# Sheet4.net
KiCad netlist of a schematic drawn in Altium Designer
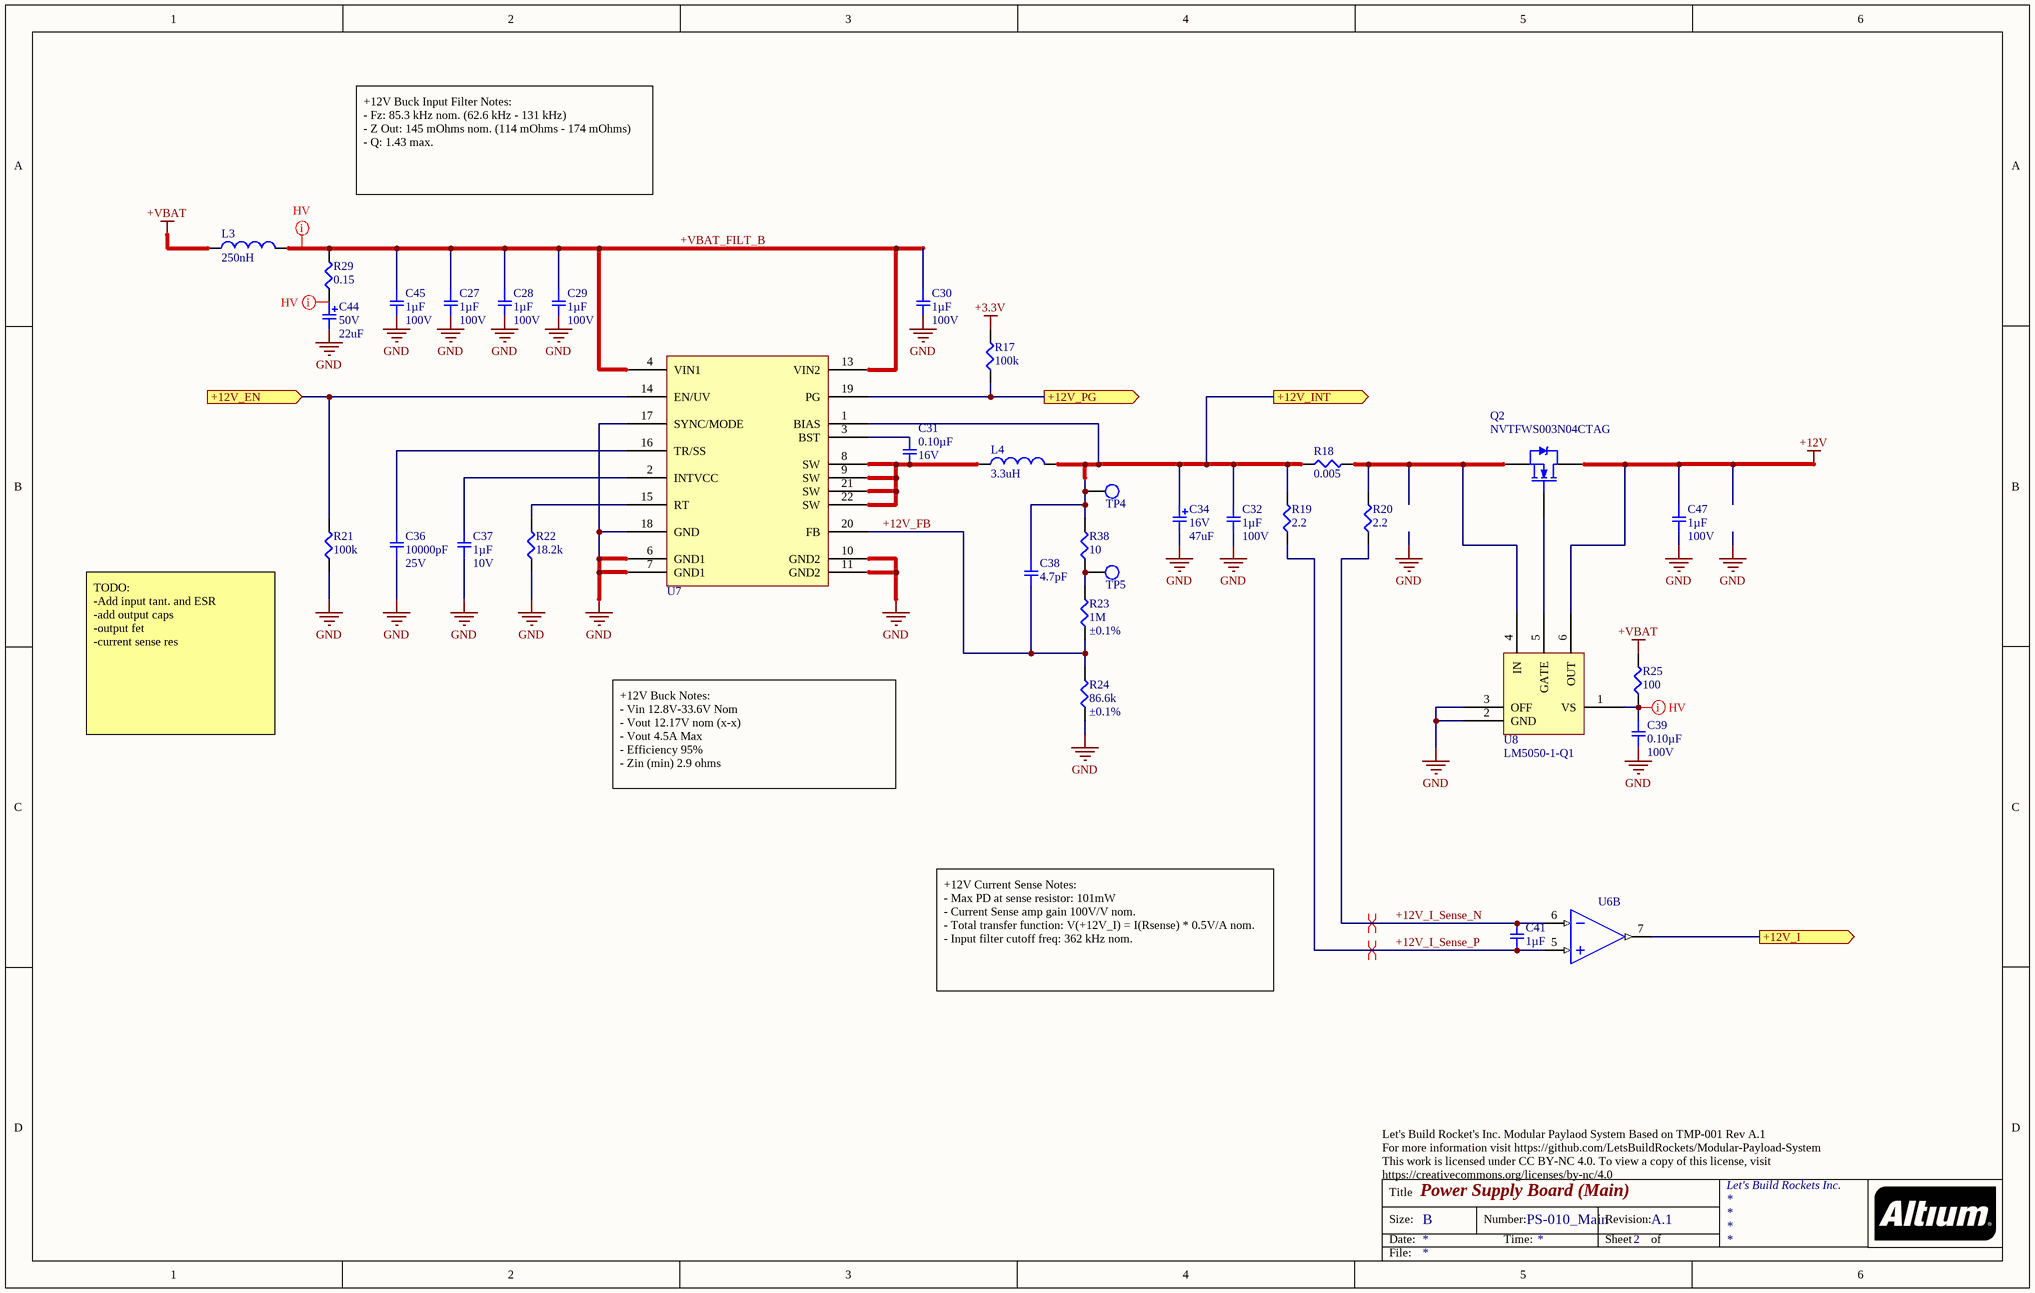
[diagram p0: Sheet4.SchDoc]

(export (version "E")
  (design (tool "Eeschema 10.0.6"))
  (components
    (comp (ref "C27")
      (value "1µF")
      (footprint "SMD-0805C")
      (description "CAP CER 1UF 100V X7S 0805")
      (fields
        (field (name "DIGI-KEY PART NUMBER") "490-10918-1-ND")
        (field (name "PART NUMBER") "GRJ21BC72A105KE11L")
        (field (name "VOLTAGE") "100V")
      )
      (libsource (lib "capacitor_murata_0805") (part "GRJ21BC72A105KE11L"))
    )
    (comp (ref "C28")
      (value "1µF")
      (footprint "SMD-0805C")
      (description "CAP CER 1UF 100V X7S 0805")
      (fields
        (field (name "DIGI-KEY PART NUMBER") "490-10918-1-ND")
        (field (name "PART NUMBER") "GRJ21BC72A105KE11L")
        (field (name "VOLTAGE") "100V")
      )
      (libsource (lib "capacitor_murata_0805") (part "GRJ21BC72A105KE11L"))
    )
    (comp (ref "C29")
      (value "1µF")
      (footprint "SMD-0805C")
      (description "CAP CER 1UF 100V X7S 0805")
      (fields
        (field (name "DIGI-KEY PART NUMBER") "490-10918-1-ND")
        (field (name "PART NUMBER") "GRJ21BC72A105KE11L")
        (field (name "VOLTAGE") "100V")
      )
      (libsource (lib "capacitor_murata_0805") (part "GRJ21BC72A105KE11L"))
    )
    (comp (ref "C30")
      (value "1µF")
      (footprint "SMD-0805C")
      (description "CAP CER 1UF 100V X7S 0805")
      (fields
        (field (name "DIGI-KEY PART NUMBER") "490-10918-1-ND")
        (field (name "PART NUMBER") "GRJ21BC72A105KE11L")
        (field (name "VOLTAGE") "100V")
      )
      (libsource (lib "capacitor_murata_0805") (part "GRJ21BC72A105KE11L"))
    )
    (comp (ref "C31")
      (value "0.10µF")
      (footprint "SMD-0402C")
      (description "CAP CER 0.1UF 16V X7R 0402")
      (fields
        (field (name "DIGI-KEY PART NUMBER") "490-4759-1-ND")
        (field (name "PART NUMBER") "GCM155R71C104KA55D")
        (field (name "VOLTAGE") "16V")
      )
      (libsource (lib "capacitor_murata_0402") (part "GCM155R71C104KA55D"))
    )
    (comp (ref "C32")
      (value "1µF")
      (footprint "SMD-0805C")
      (description "CAP CER 1UF 100V X7S 0805")
      (fields
        (field (name "DIGI-KEY PART NUMBER") "490-10918-1-ND")
        (field (name "PART NUMBER") "GRJ21BC72A105KE11L")
        (field (name "VOLTAGE") "100V")
      )
      (libsource (lib "capacitor_murata_0805") (part "GRJ21BC72A105KE11L"))
    )
    (comp (ref "C34")
      (value "47uF")
      (footprint "KEMET W - CAPMP7343X15N")
      (fields (field (name "VOLTAGE") "16V") (field (name "Comment") "T521W476M016ATE045"))
      (libsource (lib "KEMET") (part "T521W476M016ATE045"))
    )
    (comp (ref "C36")
      (value "10000pF")
      (footprint "SMD-0402C")
      (description "CAP CER 10000PF 25V X7R 0402")
      (fields
        (field (name "DIGI-KEY PART NUMBER") "490-6043-1-ND")
        (field (name "PART NUMBER") "GCM155R71E103KA37D")
        (field (name "VOLTAGE") "25V")
      )
      (libsource (lib "capacitor_murata_0402") (part "GCM155R71E103KA37D"))
    )
    (comp (ref "C37")
      (value "1µF")
      (footprint "SMD-0402C")
      (description "CAP CER 1UF 10V X7S 0402")
      (fields
        (field (name "DIGI-KEY PART NUMBER") "490-13409-1-ND")
        (field (name "PART NUMBER") "GCM155C71A105KE38D")
        (field (name "VOLTAGE") "10V")
      )
      (libsource (lib "capacitor_murata_0402") (part "GCM155C71A105KE38D"))
    )
    (comp (ref "C38")
      (value "4.7pF")
      (footprint "SMD-0402C")
      (description "CAP CER 4.7PF 50V NP0 0402")
      (fields
        (field (name "DIGI-KEY PART NUMBER") "490-12652-1-ND")
        (field (name "PART NUMBER") "GCM1555C1H4R7CA16D")
      )
      (libsource (lib "capacitor_murata_0402") (part "GCM1555C1H4R7CA16D"))
    )
    (comp (ref "C39")
      (value "0.10µF")
      (footprint "SMD-0603C")
      (description "CAP CER 0.1UF 100V X7R 0603")
      (fields
        (field (name "DIGI-KEY PART NUMBER") "490-3285-1-ND")
        (field (name "PART NUMBER") "GRM188R72A104KA35D")
        (field (name "VOLTAGE") "100V")
      )
      (libsource (lib "capacitor_murata_0603") (part "GRM188R72A104KA35D"))
    )
    (comp (ref "C41")
      (value "1µF")
      (footprint "SMD-0402C")
      (description "CAP CER 1UF 10V X7S 0402")
      (fields
        (field (name "DIGI-KEY PART NUMBER") "490-13409-1-ND")
        (field (name "PART NUMBER") "GCM155C71A105KE38D")
      )
      (libsource (lib "capacitor_murata_0402") (part "GCM155C71A105KE38D"))
    )
    (comp (ref "C44")
      (value "22uF")
      (footprint "KEMET D - CAPMP7343X31N")
      (fields (field (name "VOLTAGE") "50V") (field (name "Comment") "T521D226M050ATE090"))
      (libsource (lib "KEMET") (part "T521D226M050ATE090"))
    )
    (comp (ref "C45")
      (value "1µF")
      (footprint "SMD-0805C")
      (description "CAP CER 1UF 100V X7S 0805")
      (fields
        (field (name "DIGI-KEY PART NUMBER") "490-10918-1-ND")
        (field (name "PART NUMBER") "GRJ21BC72A105KE11L")
        (field (name "VOLTAGE") "100V")
      )
      (libsource (lib "capacitor_murata_0805") (part "GRJ21BC72A105KE11L"))
    )
    (comp (ref "C47")
      (value "1µF")
      (footprint "SMD-0805C")
      (description "CAP CER 1UF 100V X7S 0805")
      (fields
        (field (name "DIGI-KEY PART NUMBER") "490-10918-1-ND")
        (field (name "PART NUMBER") "GRJ21BC72A105KE11L")
        (field (name "VOLTAGE") "100V")
      )
      (libsource (lib "capacitor_murata_0805") (part "GRJ21BC72A105KE11L"))
    )
    (comp (ref "L3")
      (value "250nH")
      (footprint "INDM4040X21N (XGL4020)")
      (fields (field (name "Comment") "XGL4020-251ME"))
      (libsource (lib "ModularPayload") (part "XGL4020-251ME"))
    )
    (comp (ref "L4")
      (value "3.3uH")
      (footprint "INDM7050X50N (Wurth)")
      (fields (field (name "TOLERANCE") "20%") (field (name "Comment") "744314330"))
      (libsource (lib "ModularPayload") (part "744314330"))
    )
    (comp (ref "Q2")
      (value "NVTFWS003N04CTAG")
      (footprint "DFN065P305X80-8N")
      (libsource (lib "ModularPayload") (part "NVTFWS003N04CTAG"))
    )
    (comp (ref "R17")
      (value "100k")
      (footprint "SMD-0402-RES")
      (description "RES SMD 100K OHM 5% 1/10W 0402")
      (fields (field (name "PART NUMBER") "ERJ-2GEJ104X") (field (name "DIGI-KEY PART NUMBER") "P100KJCT-ND"))
      (libsource (lib "Panasonic_ERJ_0402") (part "ERJ-2GEJ104X"))
    )
    (comp (ref "R18")
      (value "0.005")
      (footprint "SMD-0603-RES")
      (description "RES SMD 0.005 OHM 1% 1/4W 0603")
      (fields
        (field (name "PART NUMBER") "ERJ-3LWFR005V")
        (field (name "DIGI-KEY PART NUMBER") "P19182CT-ND")
      )
      (libsource (lib "Panasonic_ERJ_0603") (part "ERJ-3LWFR005V"))
    )
    (comp (ref "R19")
      (value "2.2")
      (footprint "SMD-0603-RES")
      (description "RES SMD 2.2 OHM 1% 1/10W 0603")
      (fields (field (name "PART NUMBER") "ERJ-3RQF2R2V") (field (name "DIGI-KEY PART NUMBER") "P2.2AJCT-ND"))
      (libsource (lib "Panasonic_ERJ_0603") (part "ERJ-3RQF2R2V"))
    )
    (comp (ref "R20")
      (value "2.2")
      (footprint "SMD-0603-RES")
      (description "RES SMD 2.2 OHM 1% 1/10W 0603")
      (fields (field (name "PART NUMBER") "ERJ-3RQF2R2V") (field (name "DIGI-KEY PART NUMBER") "P2.2AJCT-ND"))
      (libsource (lib "Panasonic_ERJ_0603") (part "ERJ-3RQF2R2V"))
    )
    (comp (ref "R21")
      (value "100k")
      (footprint "SMD-0402-RES")
      (description "RES SMD 100K OHM 5% 1/10W 0402")
      (fields (field (name "PART NUMBER") "ERJ-2GEJ104X") (field (name "DIGI-KEY PART NUMBER") "P100KJCT-ND"))
      (libsource (lib "Panasonic_ERJ_0402") (part "ERJ-2GEJ104X"))
    )
    (comp (ref "R22")
      (value "18.2k")
      (footprint "SMD-0402-RES")
      (description "RES SMD 18.2K OHM 1% 1/10W 0402")
      (fields
        (field (name "PART NUMBER") "ERJ-2RKF1822X")
        (field (name "DIGI-KEY PART NUMBER") "P18.2KLCT-ND")
      )
      (libsource (lib "Panasonic_ERJ_0402") (part "ERJ-2RKF1822X"))
    )
    (comp (ref "R23")
      (value "1M")
      (footprint "SMD-0805-RES")
      (description "RES SMD 1M OHM 0.1% 1/4W 0805")
      (fields
        (field (name "PART NUMBER") "ERJ-PB6B1004V")
        (field (name "DIGI-KEY PART NUMBER") "P20936CT-ND")
        (field (name "TOLERANCE") "±0.1%")
      )
      (libsource (lib "Panasonic_ERJ_0805") (part "ERJ-PB6B1004V"))
    )
    (comp (ref "R24")
      (value "86.6k")
      (footprint "SMD-0805-RES")
      (description "RES SMD 86.6k OHM 0.1% 1/4W 0805")
      (fields
        (field (name "PART NUMBER") "ERJ-PB6B8662V")
        (field (name "DIGI-KEY PART NUMBER") "P20815CT-ND")
        (field (name "TOLERANCE") "±0.1%")
      )
      (libsource (lib "Panasonic_ERJ_0805") (part "ERJ-PB6B8662V"))
    )
    (comp (ref "R25")
      (value "100")
      (footprint "SMD-0402-RES")
      (description "RES SMD 100 OHM 5% 1/10W 0402")
      (fields (field (name "PART NUMBER") "ERJ-2GEJ101X") (field (name "DIGI-KEY PART NUMBER") "P100JCT-ND"))
      (libsource (lib "Panasonic_ERJ_0402") (part "ERJ-2GEJ101X"))
    )
    (comp (ref "R29")
      (value "0.15")
      (footprint "SMD-0603-RES")
      (description "RES SMD 0.15 OHM 5% 1/4W 0603")
      (fields (field (name "PART NUMBER") "ERJ-3BSJR15V") (field (name "DIGI-KEY PART NUMBER") "P17248CT-ND"))
      (libsource (lib "Panasonic_ERJ_0603") (part "ERJ-3BSJR15V"))
    )
    (comp (ref "R38")
      (value "10")
      (footprint "SMD-0402-RES")
      (description "RES SMD 10 OHM 5% 1/10W 0402")
      (fields (field (name "PART NUMBER") "ERJ-2GEJ100X") (field (name "DIGI-KEY PART NUMBER") "P10JCT-ND"))
      (libsource (lib "Panasonic_ERJ_0402") (part "ERJ-2GEJ100X"))
    )
    (comp (ref "TP4") (value "TP") (footprint "TP_SMD_40") (libsource (lib "TP") (part "TP")))
    (comp (ref "TP5") (value "TP") (footprint "TP_SMD_40") (libsource (lib "TP") (part "TP")))
    (comp (ref "U6")
      (value "INA2180A3IDGKT")
      (footprint "TSOP65P490X110-8N")
      (libsource (lib "ModularPayload") (part "INA2180A3IDGKT"))
    )
    (comp (ref "U7")
      (value "LT8640")
      (footprint "QFN50P300X400X80_HS-21N (LT8640)")
      (libsource (lib "ModularPayload") (part "LT8640"))
    )
    (comp (ref "U8")
      (value "LM5050-1-Q1")
      (footprint "SOT95P280X110-6N")
      (libsource (lib "ModularPayload") (part "LM5050-1-Q1"))
    )
  )
  (nets
    (net (code "1") (name "+3.3V") (class "Default")
      (node (ref "R17") (pin "2") (pinfunction "2_2") (pintype "passive"))
    )
    (net (code "2") (name "+12V") (class "Default")
      (node (ref "C47") (pin "1") (pinfunction "1_1") (pintype "passive"))
      (node (ref "Q2") (pin "D") (pinfunction "D_D") (pintype "passive"))
      (node (ref "U8") (pin "6") (pinfunction "OUT_6") (pintype "passive"))
    )
    (net (code "3") (name "+VBAT") (class "Default")
      (node (ref "L3") (pin "1") (pinfunction "1_1") (pintype "passive"))
      (node (ref "R25") (pin "2") (pinfunction "2_2") (pintype "passive"))
    )
    (net (code "4") (name "/+12V_EN") (class "Default")
      (node (ref "R21") (pin "2") (pinfunction "2_2") (pintype "passive"))
      (node (ref "U7") (pin "14") (pinfunction "EN/UV_14") (pintype "passive"))
    )
    (net (code "5") (name "/+12V_FB") (class "Default")
      (node (ref "C38") (pin "2") (pinfunction "2_2") (pintype "passive"))
      (node (ref "R23") (pin "1") (pinfunction "1_1") (pintype "passive"))
      (node (ref "R24") (pin "2") (pinfunction "2_2") (pintype "passive"))
      (node (ref "U7") (pin "20") (pinfunction "FB_20") (pintype "passive"))
    )
    (net (code "6") (name "/+12V_I") (class "Default")
      (node (ref "U6") (pin "7") (pinfunction "OUT2_7") (pintype "output"))
    )
    (net (code "7") (name "/+12V_INT") (class "Default")
      (node (ref "C32") (pin "1") (pinfunction "1_1") (pintype "passive"))
      (node (ref "C34") (pin "1") (pinfunction "1_1") (pintype "passive"))
      (node (ref "C38") (pin "1") (pinfunction "1_1") (pintype "passive"))
      (node (ref "L4") (pin "2") (pinfunction "2_2") (pintype "passive"))
      (node (ref "R18") (pin "1") (pinfunction "1_1") (pintype "passive"))
      (node (ref "R19") (pin "2") (pinfunction "2_2") (pintype "passive"))
      (node (ref "R38") (pin "2") (pinfunction "2_2") (pintype "passive"))
      (node (ref "TP4") (pin "1") (pintype "passive"))
      (node (ref "U7") (pin "1") (pinfunction "BIAS_1") (pintype "passive"))
    )
    (net (code "8") (name "/+12V_I_Sense_N") (class "Default")
      (node (ref "C41") (pin "2") (pinfunction "2_2") (pintype "passive"))
      (node (ref "R20") (pin "1") (pinfunction "1_1") (pintype "passive"))
      (node (ref "U6") (pin "6") (pinfunction "IN-2_6") (pintype "input"))
    )
    (net (code "9") (name "/+12V_I_Sense_P") (class "Default")
      (node (ref "C41") (pin "1") (pinfunction "1_1") (pintype "passive"))
      (node (ref "R19") (pin "1") (pinfunction "1_1") (pintype "passive"))
      (node (ref "U6") (pin "5") (pinfunction "IN+2_5") (pintype "input"))
    )
    (net (code "10") (name "/+12V_PG") (class "Default")
      (node (ref "R17") (pin "1") (pinfunction "1_1") (pintype "passive"))
      (node (ref "U7") (pin "19") (pinfunction "PG_19") (pintype "passive"))
    )
    (net (code "11") (name "/+VBAT_FILT_B") (class "Default")
      (node (ref "C27") (pin "1") (pinfunction "1_1") (pintype "passive"))
      (node (ref "C28") (pin "1") (pinfunction "1_1") (pintype "passive"))
      (node (ref "C29") (pin "1") (pinfunction "1_1") (pintype "passive"))
      (node (ref "C30") (pin "1") (pinfunction "1_1") (pintype "passive"))
      (node (ref "C45") (pin "1") (pinfunction "1_1") (pintype "passive"))
      (node (ref "L3") (pin "2") (pinfunction "2_2") (pintype "passive"))
      (node (ref "R29") (pin "2") (pinfunction "2_2") (pintype "passive"))
      (node (ref "U7") (pin "13") (pinfunction "VIN2_13") (pintype "passive"))
      (node (ref "U7") (pin "4") (pinfunction "VIN1_4") (pintype "passive"))
    )
    (net (code "12") (name "GND") (class "Default")
      (node (ref "C27") (pin "2") (pinfunction "2_2") (pintype "passive"))
      (node (ref "C28") (pin "2") (pinfunction "2_2") (pintype "passive"))
      (node (ref "C29") (pin "2") (pinfunction "2_2") (pintype "passive"))
      (node (ref "C30") (pin "2") (pinfunction "2_2") (pintype "passive"))
      (node (ref "C32") (pin "2") (pinfunction "2_2") (pintype "passive"))
      (node (ref "C34") (pin "2") (pinfunction "2_2") (pintype "passive"))
      (node (ref "C36") (pin "1") (pinfunction "1_1") (pintype "passive"))
      (node (ref "C37") (pin "1") (pinfunction "1_1") (pintype "passive"))
      (node (ref "C39") (pin "1") (pinfunction "1_1") (pintype "passive"))
      (node (ref "C44") (pin "2") (pinfunction "2_2") (pintype "passive"))
      (node (ref "C45") (pin "2") (pinfunction "2_2") (pintype "passive"))
      (node (ref "C47") (pin "2") (pinfunction "2_2") (pintype "passive"))
      (node (ref "R21") (pin "1") (pinfunction "1_1") (pintype "passive"))
      (node (ref "R22") (pin "1") (pinfunction "1_1") (pintype "passive"))
      (node (ref "R24") (pin "1") (pinfunction "1_1") (pintype "passive"))
      (node (ref "U7") (pin "10") (pinfunction "GND2_10") (pintype "passive"))
      (node (ref "U7") (pin "11") (pinfunction "GND2_11") (pintype "passive"))
      (node (ref "U7") (pin "17") (pinfunction "SYNC/MODE_17") (pintype "passive"))
      (node (ref "U7") (pin "18") (pinfunction "GND_18") (pintype "passive"))
      (node (ref "U7") (pin "6") (pinfunction "GND1_6") (pintype "passive"))
      (node (ref "U7") (pin "7") (pinfunction "GND1_7") (pintype "passive"))
      (node (ref "U8") (pin "2") (pinfunction "GND_2") (pintype "passive"))
      (node (ref "U8") (pin "3") (pinfunction "OFF_3") (pintype "passive"))
    )
    (net (code "13") (name "Net-(C31-Pad2)") (class "Default")
      (node (ref "C31") (pin "2") (pinfunction "2_2") (pintype "passive"))
      (node (ref "L4") (pin "1") (pinfunction "1_1") (pintype "passive"))
      (node (ref "U7") (pin "21") (pinfunction "SW_21") (pintype "passive"))
      (node (ref "U7") (pin "22") (pinfunction "SW_22") (pintype "passive"))
      (node (ref "U7") (pin "8") (pinfunction "SW_8") (pintype "passive"))
      (node (ref "U7") (pin "9") (pinfunction "SW_9") (pintype "passive"))
    )
    (net (code "14") (name "Net-(C44-Pad1)") (class "Default")
      (node (ref "C44") (pin "1") (pinfunction "1_1") (pintype "passive"))
      (node (ref "R29") (pin "1") (pinfunction "1_1") (pintype "passive"))
    )
    (net (code "15") (name "Net-(R23-Pad2)") (class "Default")
      (node (ref "R23") (pin "2") (pinfunction "2_2") (pintype "passive"))
      (node (ref "R38") (pin "1") (pinfunction "1_1") (pintype "passive"))
      (node (ref "TP5") (pin "1") (pintype "passive"))
    )
    (net (code "16") (name "Net-(U7-BST)") (class "Default")
      (node (ref "C31") (pin "1") (pinfunction "1_1") (pintype "passive"))
      (node (ref "U7") (pin "3") (pinfunction "BST_3") (pintype "passive"))
    )
    (net (code "17") (name "Net-(U7-INTVCC)") (class "Default")
      (node (ref "C37") (pin "2") (pinfunction "2_2") (pintype "passive"))
      (node (ref "U7") (pin "2") (pinfunction "INTVCC_2") (pintype "passive"))
    )
    (net (code "18") (name "Net-(U7-RT)") (class "Default")
      (node (ref "R22") (pin "2") (pinfunction "2_2") (pintype "passive"))
      (node (ref "U7") (pin "15") (pinfunction "RT_15") (pintype "passive"))
    )
    (net (code "19") (name "Net-(U7-TR{slash}SS)") (class "Default")
      (node (ref "C36") (pin "2") (pinfunction "2_2") (pintype "passive"))
      (node (ref "U7") (pin "16") (pinfunction "TR/SS_16") (pintype "passive"))
    )
    (net (code "20") (name "Net-(U8-GATE)") (class "Default")
      (node (ref "Q2") (pin "G") (pinfunction "G_G") (pintype "passive"))
      (node (ref "U8") (pin "5") (pinfunction "GATE_5") (pintype "passive"))
    )
    (net (code "21") (name "Net-(U8-IN)") (class "Default")
      (node (ref "Q2") (pin "S") (pinfunction "S_S") (pintype "passive"))
      (node (ref "R18") (pin "2") (pinfunction "2_2") (pintype "passive"))
      (node (ref "R20") (pin "2") (pinfunction "2_2") (pintype "passive"))
      (node (ref "U8") (pin "4") (pinfunction "IN_4") (pintype "passive"))
    )
    (net (code "22") (name "Net-(U8-VS)") (class "Default")
      (node (ref "C39") (pin "2") (pinfunction "2_2") (pintype "passive"))
      (node (ref "R25") (pin "1") (pinfunction "1_1") (pintype "passive"))
      (node (ref "U8") (pin "1") (pinfunction "VS_1") (pintype "passive"))
    )
  )
)
